# main.net
KiCad netlist of a schematic drawn in EAGLE
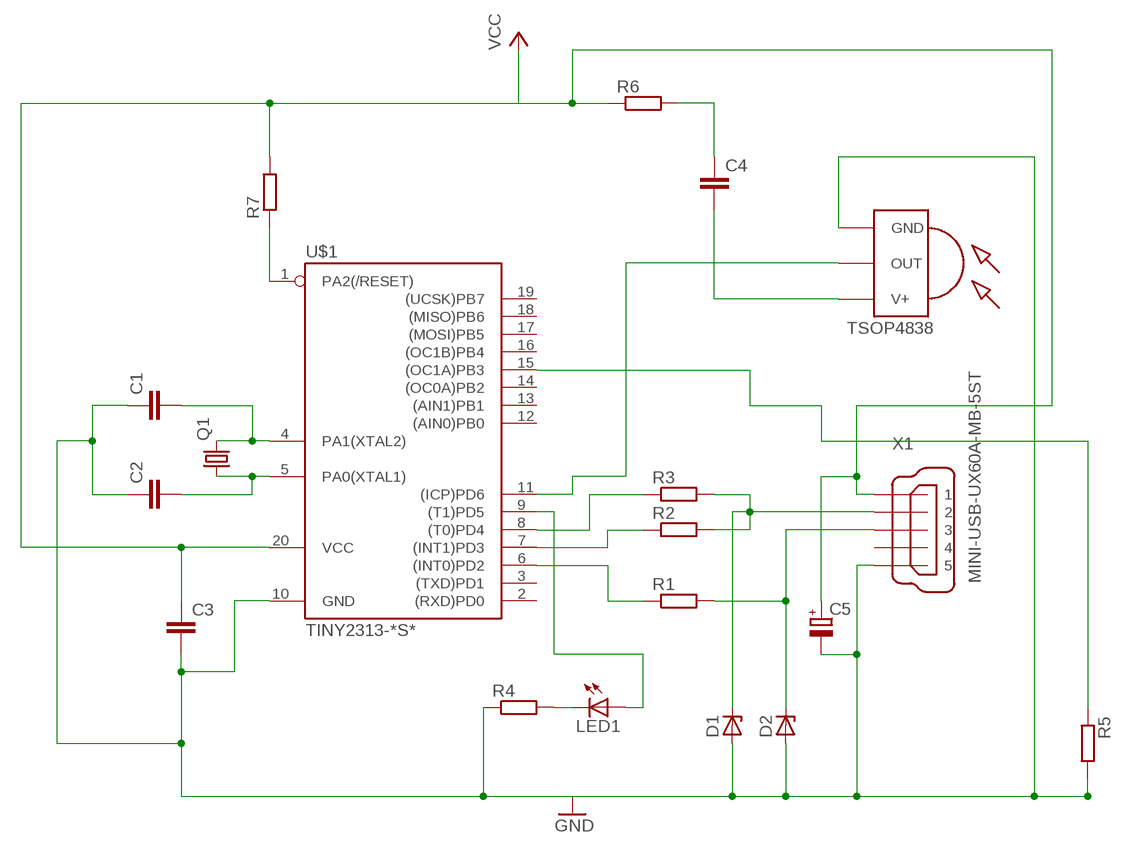
[diagram p0: schematic, sheet 1]

(export (version "E")
  (design (tool "Eeschema 10.0.6"))
  (components
    (comp (ref "C1")
      (value "C-EUC0603")
      (footprint "eagle-import:C0603")
      (libsource (lib "eagle-import") (part "C-EUC0603"))
    )
    (comp (ref "C2")
      (value "C-EUC0603")
      (footprint "eagle-import:C0603")
      (libsource (lib "eagle-import") (part "C-EUC0603"))
    )
    (comp (ref "C3")
      (value "C-EUC0603")
      (footprint "eagle-import:C0603")
      (libsource (lib "eagle-import") (part "C-EUC0603"))
    )
    (comp (ref "C4")
      (value "C-EUC0603")
      (footprint "eagle-import:C0603")
      (libsource (lib "eagle-import") (part "C-EUC0603"))
    )
    (comp (ref "C5")
      (value "CPOL-EUE2.5-6")
      (footprint "eagle-import:E2,5-6")
      (libsource (lib "eagle-import") (part "CPOL-EUE2.5-6"))
    )
    (comp (ref "D1")
      (value "ZENER-DIODESOD80C")
      (footprint "eagle-import:SOD80C")
      (libsource (lib "eagle-import") (part "ZENER-DIODESOD80C"))
    )
    (comp (ref "D2")
      (value "ZENER-DIODESOD80C")
      (footprint "eagle-import:SOD80C")
      (libsource (lib "eagle-import") (part "ZENER-DIODESOD80C"))
    )
    (comp (ref "LED1")
      (value "LED3MM")
      (footprint "eagle-import:LED3MM")
      (libsource (lib "eagle-import") (part "LED3MM"))
    )
    (comp (ref "Q1")
      (value "CRYSTALHC49U70")
      (footprint "eagle-import:HC49U70")
      (libsource (lib "eagle-import") (part "CRYSTALHC49U70"))
    )
    (comp (ref "R1")
      (value "R-EU_R0603")
      (footprint "eagle-import:R0603")
      (libsource (lib "eagle-import") (part "R-EU_R0603"))
    )
    (comp (ref "R2")
      (value "R-EU_R0603")
      (footprint "eagle-import:R0603")
      (libsource (lib "eagle-import") (part "R-EU_R0603"))
    )
    (comp (ref "R3")
      (value "R-EU_R0603")
      (footprint "eagle-import:R0603")
      (libsource (lib "eagle-import") (part "R-EU_R0603"))
    )
    (comp (ref "R4")
      (value "R-EU_R0603")
      (footprint "eagle-import:R0603")
      (libsource (lib "eagle-import") (part "R-EU_R0603"))
    )
    (comp (ref "R5")
      (value "R-EU_R0603")
      (footprint "eagle-import:R0603")
      (libsource (lib "eagle-import") (part "R-EU_R0603"))
    )
    (comp (ref "R6")
      (value "R-EU_R0603")
      (footprint "eagle-import:R0603")
      (libsource (lib "eagle-import") (part "R-EU_R0603"))
    )
    (comp (ref "R7")
      (value "R-EU_R0603")
      (footprint "eagle-import:R0603")
      (libsource (lib "eagle-import") (part "R-EU_R0603"))
    )
    (comp (ref "U$1")
      (value "TINY2313-*S*")
      (footprint "eagle-import:SO20L$")
      (libsource (lib "eagle-import") (part "TINY2313-S"))
    )
    (comp (ref "U$2")
      (value "TSOP4838")
      (footprint "eagle-import:TSOP18XX")
      (libsource (lib "eagle-import") (part "TSOP4838"))
    )
    (comp (ref "X1")
      (value "MINI-USB-UX60A-MB-5ST")
      (footprint "eagle-import:UX60A-MB-5ST")
      (libsource (lib "eagle-import") (part "MINI-USB-UX60A-MB-5ST"))
    )
  )
  (nets
    (net (code "1") (name "GND") (class "Default")
      (node (ref "C1") (pin "1") (pinfunction "1_1") (pintype "passive"))
      (node (ref "C2") (pin "1") (pinfunction "1_1") (pintype "passive"))
      (node (ref "C3") (pin "2") (pinfunction "2_2") (pintype "passive"))
      (node (ref "C5") (pin "-") (pinfunction "-_-") (pintype "passive"))
      (node (ref "D1") (pin "A") (pinfunction "A_A") (pintype "passive"))
      (node (ref "D2") (pin "A") (pinfunction "A_A") (pintype "passive"))
      (node (ref "R4") (pin "1") (pinfunction "1_1") (pintype "passive"))
      (node (ref "R5") (pin "2") (pinfunction "2_2") (pintype "passive"))
      (node (ref "U$1") (pin "10") (pinfunction "GND_10") (pintype "power_in"))
      (node (ref "U$2") (pin "GND") (pinfunction "GND_GND") (pintype "bidirectional"))
      (node (ref "X1") (pin "5") (pinfunction "5_5") (pintype "input"))
    )
    (net (code "2") (name "Net-(C4-Pad1)") (class "Default")
      (node (ref "C4") (pin "1") (pinfunction "1_1") (pintype "passive"))
      (node (ref "R6") (pin "2") (pinfunction "2_2") (pintype "passive"))
    )
    (net (code "3") (name "Net-(D1-PadC)") (class "Default")
      (node (ref "D1") (pin "C") (pinfunction "C_C") (pintype "passive"))
      (node (ref "R2") (pin "2") (pinfunction "2_2") (pintype "passive"))
      (node (ref "R3") (pin "2") (pinfunction "2_2") (pintype "passive"))
      (node (ref "X1") (pin "2") (pinfunction "2_2") (pintype "input"))
    )
    (net (code "4") (name "Net-(D2-PadC)") (class "Default")
      (node (ref "D2") (pin "C") (pinfunction "C_C") (pintype "passive"))
      (node (ref "R1") (pin "2") (pinfunction "2_2") (pintype "passive"))
      (node (ref "X1") (pin "3") (pinfunction "3_3") (pintype "input"))
    )
    (net (code "5") (name "Net-(LED1-C)") (class "Default")
      (node (ref "LED1") (pin "K") (pinfunction "C_K") (pintype "passive"))
      (node (ref "R4") (pin "2") (pinfunction "2_2") (pintype "passive"))
    )
    (net (code "6") (name "Net-(U$1-(ICP)PD6)") (class "Default")
      (node (ref "U$1") (pin "11") (pinfunction "(ICP)PD6_11") (pintype "bidirectional"))
      (node (ref "U$2") (pin "OUT") (pinfunction "OUT_OUT") (pintype "bidirectional"))
    )
    (net (code "7") (name "Net-(U$1-(INT0)PD2)") (class "Default")
      (node (ref "R1") (pin "1") (pinfunction "1_1") (pintype "passive"))
      (node (ref "U$1") (pin "6") (pinfunction "(INT0)PD2_6") (pintype "bidirectional"))
    )
    (net (code "8") (name "Net-(U$1-(INT1)PD3)") (class "Default")
      (node (ref "R2") (pin "1") (pinfunction "1_1") (pintype "passive"))
      (node (ref "U$1") (pin "7") (pinfunction "(INT1)PD3_7") (pintype "bidirectional"))
    )
    (net (code "9") (name "Net-(U$1-(OC1A)PB3)") (class "Default")
      (node (ref "R5") (pin "1") (pinfunction "1_1") (pintype "passive"))
      (node (ref "U$1") (pin "15") (pinfunction "(OC1A)PB3_15") (pintype "bidirectional"))
    )
    (net (code "10") (name "Net-(U$1-(T0)PD4)") (class "Default")
      (node (ref "R3") (pin "1") (pinfunction "1_1") (pintype "passive"))
      (node (ref "U$1") (pin "8") (pinfunction "(T0)PD4_8") (pintype "bidirectional"))
    )
    (net (code "11") (name "Net-(U$1-(T1)PD5)") (class "Default")
      (node (ref "LED1") (pin "A") (pinfunction "A_A") (pintype "passive"))
      (node (ref "U$1") (pin "9") (pinfunction "(T1)PD5_9") (pintype "bidirectional"))
    )
    (net (code "12") (name "Net-(U$1-PA0(XTAL1))") (class "Default")
      (node (ref "C2") (pin "2") (pinfunction "2_2") (pintype "passive"))
      (node (ref "Q1") (pin "1") (pinfunction "1_1") (pintype "passive"))
      (node (ref "U$1") (pin "5") (pinfunction "PA0(XTAL1)_5") (pintype "bidirectional"))
    )
    (net (code "13") (name "Net-(U$1-PA1(XTAL2))") (class "Default")
      (node (ref "C1") (pin "2") (pinfunction "2_2") (pintype "passive"))
      (node (ref "Q1") (pin "2") (pinfunction "2_2") (pintype "passive"))
      (node (ref "U$1") (pin "4") (pinfunction "PA1(XTAL2)_4") (pintype "bidirectional"))
    )
    (net (code "14") (name "Net-(U$1-PA2({slash}RESET))") (class "Default")
      (node (ref "R7") (pin "1") (pinfunction "1_1") (pintype "passive"))
      (node (ref "U$1") (pin "1") (pinfunction "PA2(/RESET)_1") (pintype "input"))
    )
    (net (code "15") (name "Net-(U$2-V+)") (class "Default")
      (node (ref "C4") (pin "2") (pinfunction "2_2") (pintype "passive"))
      (node (ref "U$2") (pin "VCC") (pinfunction "V+_VCC") (pintype "bidirectional"))
    )
    (net (code "16") (name "VCC") (class "Default")
      (node (ref "C3") (pin "1") (pinfunction "1_1") (pintype "passive"))
      (node (ref "C5") (pin "+") (pinfunction "+_+") (pintype "passive"))
      (node (ref "R6") (pin "1") (pinfunction "1_1") (pintype "passive"))
      (node (ref "R7") (pin "2") (pinfunction "2_2") (pintype "passive"))
      (node (ref "U$1") (pin "20") (pinfunction "VCC_20") (pintype "power_in"))
      (node (ref "X1") (pin "1") (pinfunction "1_1") (pintype "input"))
    )
    (net (code "17") (name "unconnected-(U$1-(AIN0)PB0-Pad12)") (class "Default")
      (node (ref "U$1") (pin "12") (pinfunction "(AIN0)PB0_12") (pintype "bidirectional"))
    )
    (net (code "18") (name "unconnected-(U$1-(AIN1)PB1-Pad13)") (class "Default")
      (node (ref "U$1") (pin "13") (pinfunction "(AIN1)PB1_13") (pintype "bidirectional"))
    )
    (net (code "19") (name "unconnected-(U$1-(MISO)PB6-Pad18)") (class "Default")
      (node (ref "U$1") (pin "18") (pinfunction "(MISO)PB6_18") (pintype "bidirectional"))
    )
    (net (code "20") (name "unconnected-(U$1-(MOSI)PB5-Pad17)") (class "Default")
      (node (ref "U$1") (pin "17") (pinfunction "(MOSI)PB5_17") (pintype "bidirectional"))
    )
    (net (code "21") (name "unconnected-(U$1-(OC0A)PB2-Pad14)") (class "Default")
      (node (ref "U$1") (pin "14") (pinfunction "(OC0A)PB2_14") (pintype "bidirectional"))
    )
    (net (code "22") (name "unconnected-(U$1-(OC1B)PB4-Pad16)") (class "Default")
      (node (ref "U$1") (pin "16") (pinfunction "(OC1B)PB4_16") (pintype "bidirectional"))
    )
    (net (code "23") (name "unconnected-(U$1-(RXD)PD0-Pad2)") (class "Default")
      (node (ref "U$1") (pin "2") (pinfunction "(RXD)PD0_2") (pintype "bidirectional"))
    )
    (net (code "24") (name "unconnected-(U$1-(TXD)PD1-Pad3)") (class "Default")
      (node (ref "U$1") (pin "3") (pinfunction "(TXD)PD1_3") (pintype "bidirectional"))
    )
    (net (code "25") (name "unconnected-(U$1-(UCSK)PB7-Pad19)") (class "Default")
      (node (ref "U$1") (pin "19") (pinfunction "(UCSK)PB7_19") (pintype "bidirectional"))
    )
    (net (code "26") (name "unconnected-(X1-Pad4)") (class "Default")
      (node (ref "X1") (pin "4") (pinfunction "4_4") (pintype "input"))
    )
  )
)
